# temp_sensors_array_A.net
KiCad netlist of a schematic drawn in EAGLE
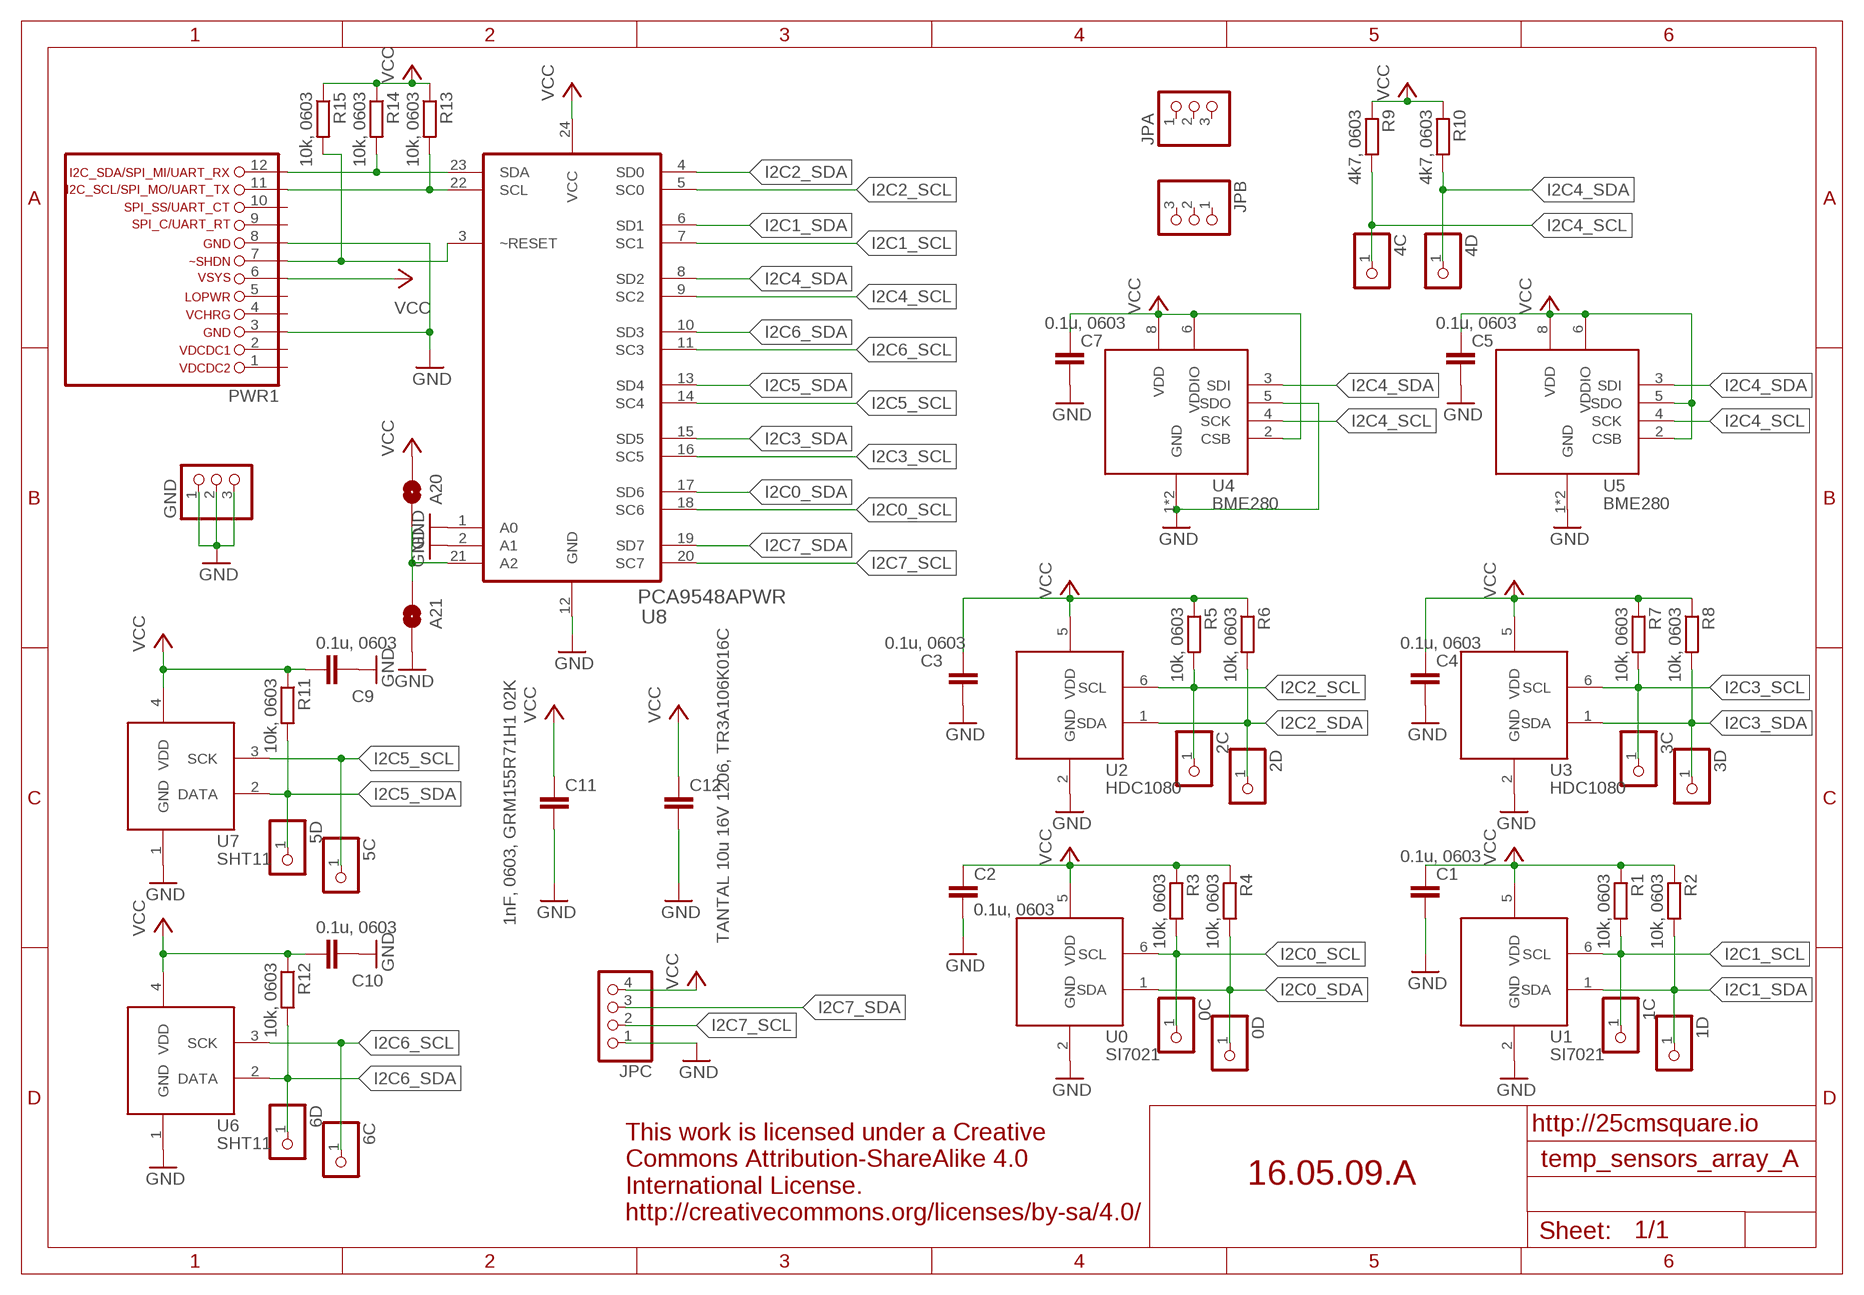
[diagram p0: schematic, sheet 1]

(export (version "E")
  (design (tool "Eeschema 10.0.6"))
  (components
    (comp (ref "0C")
      (value "PINHD-1X1")
      (footprint "eagle-import:1X01")
      (libsource (lib "eagle-import") (part "PINHD-1X1"))
    )
    (comp (ref "0D")
      (value "PINHD-1X1")
      (footprint "eagle-import:1X01")
      (libsource (lib "eagle-import") (part "PINHD-1X1"))
    )
    (comp (ref "1C")
      (value "PINHD-1X1")
      (footprint "eagle-import:1X01")
      (libsource (lib "eagle-import") (part "PINHD-1X1"))
    )
    (comp (ref "1D")
      (value "PINHD-1X1")
      (footprint "eagle-import:1X01")
      (libsource (lib "eagle-import") (part "PINHD-1X1"))
    )
    (comp (ref "2C")
      (value "PINHD-1X1")
      (footprint "eagle-import:1X01")
      (libsource (lib "eagle-import") (part "PINHD-1X1"))
    )
    (comp (ref "2D")
      (value "PINHD-1X1")
      (footprint "eagle-import:1X01")
      (libsource (lib "eagle-import") (part "PINHD-1X1"))
    )
    (comp (ref "3C")
      (value "PINHD-1X1")
      (footprint "eagle-import:1X01")
      (libsource (lib "eagle-import") (part "PINHD-1X1"))
    )
    (comp (ref "3D")
      (value "PINHD-1X1")
      (footprint "eagle-import:1X01")
      (libsource (lib "eagle-import") (part "PINHD-1X1"))
    )
    (comp (ref "4C")
      (value "PINHD-1X1")
      (footprint "eagle-import:1X01")
      (libsource (lib "eagle-import") (part "PINHD-1X1"))
    )
    (comp (ref "4D")
      (value "PINHD-1X1")
      (footprint "eagle-import:1X01")
      (libsource (lib "eagle-import") (part "PINHD-1X1"))
    )
    (comp (ref "5C")
      (value "PINHD-1X1")
      (footprint "eagle-import:1X01")
      (libsource (lib "eagle-import") (part "PINHD-1X1"))
    )
    (comp (ref "5D")
      (value "PINHD-1X1")
      (footprint "eagle-import:1X01")
      (libsource (lib "eagle-import") (part "PINHD-1X1"))
    )
    (comp (ref "6C")
      (value "PINHD-1X1")
      (footprint "eagle-import:1X01")
      (libsource (lib "eagle-import") (part "PINHD-1X1"))
    )
    (comp (ref "6D")
      (value "PINHD-1X1")
      (footprint "eagle-import:1X01")
      (libsource (lib "eagle-import") (part "PINHD-1X1"))
    )
    (comp (ref "A20")
      (value "SOLDERJUMPERNO")
      (footprint "eagle-import:SJ_2S-NO")
      (libsource (lib "eagle-import") (part "SOLDERJUMPERNO"))
    )
    (comp (ref "A21")
      (value "SOLDERJUMPERNO")
      (footprint "eagle-import:SJ_2S-NO")
      (libsource (lib "eagle-import") (part "SOLDERJUMPERNO"))
    )
    (comp (ref "C1")
      (value "0.1u, 0603")
      (footprint "eagle-import:C0603K")
      (libsource (lib "eagle-import") (part "C-EUC0603K"))
    )
    (comp (ref "C2")
      (value "0.1u, 0603")
      (footprint "eagle-import:C0603K")
      (libsource (lib "eagle-import") (part "C-EUC0603K"))
    )
    (comp (ref "C3")
      (value "0.1u, 0603")
      (footprint "eagle-import:C0603K")
      (libsource (lib "eagle-import") (part "C-EUC0603K"))
    )
    (comp (ref "C4")
      (value "0.1u, 0603")
      (footprint "eagle-import:C0603K")
      (libsource (lib "eagle-import") (part "C-EUC0603K"))
    )
    (comp (ref "C5")
      (value "0.1u, 0603")
      (footprint "eagle-import:C0603K")
      (libsource (lib "eagle-import") (part "C-EUC0603K"))
    )
    (comp (ref "C7")
      (value "0.1u, 0603")
      (footprint "eagle-import:C0603K")
      (libsource (lib "eagle-import") (part "C-EUC0603K"))
    )
    (comp (ref "C9")
      (value "0.1u, 0603")
      (footprint "eagle-import:C0603K")
      (libsource (lib "eagle-import") (part "C-EUC0603K"))
    )
    (comp (ref "C10")
      (value "0.1u, 0603")
      (footprint "eagle-import:C0603K")
      (libsource (lib "eagle-import") (part "C-EUC0603K"))
    )
    (comp (ref "C11")
      (value "1nF, 0603, GRM155R71H1 02K")
      (footprint "eagle-import:C0603K")
      (libsource (lib "eagle-import") (part "C-EUC0603K"))
    )
    (comp (ref "C12")
      (value "TANTAL 10u 16V 1206, TR3A106K016C")
      (footprint "eagle-import:C1206K")
      (libsource (lib "eagle-import") (part "resistor_C-EUC1206K"))
    )
    (comp (ref "GND")
      (value "PINHD-1X3")
      (footprint "eagle-import:1X03")
      (libsource (lib "eagle-import") (part "PINHD-1X3"))
    )
    (comp (ref "JPA")
      (value "PINHD-1X3")
      (footprint "eagle-import:1X03")
      (libsource (lib "eagle-import") (part "PINHD-1X3"))
    )
    (comp (ref "JPB")
      (value "PINHD-1X3")
      (footprint "eagle-import:1X03")
      (libsource (lib "eagle-import") (part "PINHD-1X3"))
    )
    (comp (ref "JPC")
      (value "PINHD-1X4")
      (footprint "eagle-import:1X04")
      (libsource (lib "eagle-import") (part "PINHD-1X4"))
    )
    (comp (ref "PWR1")
      (value "LIWE_12_PIN_PWR")
      (footprint "eagle-import:LIWE_12_PIN")
      (libsource (lib "eagle-import") (part "LIWE_12_PIN_PWR"))
    )
    (comp (ref "R1")
      (value "10k, 0603")
      (footprint "eagle-import:R0603")
      (libsource (lib "eagle-import") (part "R-EU_R0603"))
    )
    (comp (ref "R2")
      (value "10k, 0603")
      (footprint "eagle-import:R0603")
      (libsource (lib "eagle-import") (part "R-EU_R0603"))
    )
    (comp (ref "R3")
      (value "10k, 0603")
      (footprint "eagle-import:R0603")
      (libsource (lib "eagle-import") (part "R-EU_R0603"))
    )
    (comp (ref "R4")
      (value "10k, 0603")
      (footprint "eagle-import:R0603")
      (libsource (lib "eagle-import") (part "R-EU_R0603"))
    )
    (comp (ref "R5")
      (value "10k, 0603")
      (footprint "eagle-import:R0603")
      (libsource (lib "eagle-import") (part "R-EU_R0603"))
    )
    (comp (ref "R6")
      (value "10k, 0603")
      (footprint "eagle-import:R0603")
      (libsource (lib "eagle-import") (part "R-EU_R0603"))
    )
    (comp (ref "R7")
      (value "10k, 0603")
      (footprint "eagle-import:R0603")
      (libsource (lib "eagle-import") (part "R-EU_R0603"))
    )
    (comp (ref "R8")
      (value "10k, 0603")
      (footprint "eagle-import:R0603")
      (libsource (lib "eagle-import") (part "R-EU_R0603"))
    )
    (comp (ref "R9")
      (value "4k7, 0603")
      (footprint "eagle-import:R0603")
      (libsource (lib "eagle-import") (part "R-EU_R0603"))
    )
    (comp (ref "R10")
      (value "4k7, 0603")
      (footprint "eagle-import:R0603")
      (libsource (lib "eagle-import") (part "R-EU_R0603"))
    )
    (comp (ref "R11")
      (value "10k, 0603")
      (footprint "eagle-import:R0603")
      (libsource (lib "eagle-import") (part "R-EU_R0603"))
    )
    (comp (ref "R12")
      (value "10k, 0603")
      (footprint "eagle-import:R0603")
      (libsource (lib "eagle-import") (part "R-EU_R0603"))
    )
    (comp (ref "R13")
      (value "10k, 0603")
      (footprint "eagle-import:R0603")
      (libsource (lib "eagle-import") (part "R-EU_R0603"))
    )
    (comp (ref "R14")
      (value "10k, 0603")
      (footprint "eagle-import:R0603")
      (libsource (lib "eagle-import") (part "R-EU_R0603"))
    )
    (comp (ref "R15")
      (value "10k, 0603")
      (footprint "eagle-import:R0603")
      (libsource (lib "eagle-import") (part "R-EU_R0603"))
    )
    (comp (ref "U0")
      (value "SI7021")
      (footprint "eagle-import:SI7021")
      (libsource (lib "eagle-import") (part "SI7021"))
    )
    (comp (ref "U1")
      (value "SI7021")
      (footprint "eagle-import:SI7021")
      (libsource (lib "eagle-import") (part "SI7021"))
    )
    (comp (ref "U2")
      (value "HDC1080")
      (footprint "eagle-import:SI7021")
      (libsource (lib "eagle-import") (part "HDC1080"))
    )
    (comp (ref "U3")
      (value "HDC1080")
      (footprint "eagle-import:SI7021")
      (libsource (lib "eagle-import") (part "HDC1080"))
    )
    (comp (ref "U4")
      (value "BME280")
      (footprint "eagle-import:BME1080")
      (libsource (lib "eagle-import") (part "BME280"))
    )
    (comp (ref "U5")
      (value "BME280")
      (footprint "eagle-import:BME1080")
      (libsource (lib "eagle-import") (part "BME280"))
    )
    (comp (ref "U6")
      (value "SHT11")
      (footprint "eagle-import:SHT1X")
      (libsource (lib "eagle-import") (part "SHT11"))
    )
    (comp (ref "U7")
      (value "SHT11")
      (footprint "eagle-import:SHT1X")
      (libsource (lib "eagle-import") (part "SHT11"))
    )
    (comp (ref "U8")
      (value "PCA9548APWR")
      (footprint "eagle-import:SOP65P640X120-24N")
      (fields (field (name "MPN") "PCA9548APWR    False"))
      (libsource (lib "eagle-import") (part "PCA9548APWR"))
    )
  )
  (nets
    (net (code "1") (name "GND") (class "Default")
      (node (ref "A21") (pin "2") (pinfunction "2_2") (pintype "passive"))
      (node (ref "C1") (pin "2") (pinfunction "2_2") (pintype "passive"))
      (node (ref "C10") (pin "2") (pinfunction "2_2") (pintype "passive"))
      (node (ref "C11") (pin "2") (pinfunction "2_2") (pintype "passive"))
      (node (ref "C12") (pin "2") (pinfunction "2_2") (pintype "passive"))
      (node (ref "C2") (pin "2") (pinfunction "2_2") (pintype "passive"))
      (node (ref "C3") (pin "2") (pinfunction "2_2") (pintype "passive"))
      (node (ref "C4") (pin "2") (pinfunction "2_2") (pintype "passive"))
      (node (ref "C5") (pin "2") (pinfunction "2_2") (pintype "passive"))
      (node (ref "C7") (pin "2") (pinfunction "2_2") (pintype "passive"))
      (node (ref "C9") (pin "2") (pinfunction "2_2") (pintype "passive"))
      (node (ref "GND") (pin "1") (pinfunction "1_1") (pintype "passive"))
      (node (ref "GND") (pin "2") (pinfunction "2_2") (pintype "passive"))
      (node (ref "GND") (pin "3") (pinfunction "3_3") (pintype "passive"))
      (node (ref "JPC") (pin "1") (pinfunction "1_1") (pintype "passive"))
      (node (ref "PWR1") (pin "3") (pinfunction "3_3") (pintype "passive"))
      (node (ref "PWR1") (pin "8") (pinfunction "8_8") (pintype "passive"))
      (node (ref "U0") (pin "2") (pinfunction "GND_2") (pintype "power_in"))
      (node (ref "U1") (pin "2") (pinfunction "GND_2") (pintype "power_in"))
      (node (ref "U2") (pin "2") (pinfunction "GND_2") (pintype "power_in"))
      (node (ref "U3") (pin "2") (pinfunction "GND_2") (pintype "power_in"))
      (node (ref "U4") (pin "1") (pinfunction "GND_1") (pintype "power_in"))
      (node (ref "U4") (pin "5") (pinfunction "SDO_5") (pintype "bidirectional"))
      (node (ref "U4") (pin "7") (pinfunction "GND_7") (pintype "power_in"))
      (node (ref "U5") (pin "1") (pinfunction "GND_1") (pintype "power_in"))
      (node (ref "U5") (pin "7") (pinfunction "GND_7") (pintype "power_in"))
      (node (ref "U6") (pin "1") (pinfunction "GND_1") (pintype "power_in"))
      (node (ref "U7") (pin "1") (pinfunction "GND_1") (pintype "power_in"))
      (node (ref "U8") (pin "1") (pinfunction "A0_1") (pintype "input"))
      (node (ref "U8") (pin "12") (pinfunction "GND_12") (pintype "passive"))
      (node (ref "U8") (pin "2") (pinfunction "A1_2") (pintype "input"))
    )
    (net (code "2") (name "I2C0_SCL") (class "Default")
      (node (ref "0C") (pin "1") (pinfunction "1_1") (pintype "passive"))
      (node (ref "R3") (pin "2") (pinfunction "2_2") (pintype "passive"))
      (node (ref "U0") (pin "6") (pinfunction "SCL_6") (pintype "bidirectional"))
      (node (ref "U8") (pin "18") (pinfunction "SC6_18") (pintype "bidirectional"))
    )
    (net (code "3") (name "I2C0_SDA") (class "Default")
      (node (ref "0D") (pin "1") (pinfunction "1_1") (pintype "passive"))
      (node (ref "R4") (pin "2") (pinfunction "2_2") (pintype "passive"))
      (node (ref "U0") (pin "1") (pinfunction "SDA_1") (pintype "bidirectional"))
      (node (ref "U8") (pin "17") (pinfunction "SD6_17") (pintype "bidirectional"))
    )
    (net (code "4") (name "I2C1_SCL") (class "Default")
      (node (ref "1C") (pin "1") (pinfunction "1_1") (pintype "passive"))
      (node (ref "R1") (pin "2") (pinfunction "2_2") (pintype "passive"))
      (node (ref "U1") (pin "6") (pinfunction "SCL_6") (pintype "bidirectional"))
      (node (ref "U8") (pin "7") (pinfunction "SC1_7") (pintype "bidirectional"))
    )
    (net (code "5") (name "I2C1_SDA") (class "Default")
      (node (ref "1D") (pin "1") (pinfunction "1_1") (pintype "passive"))
      (node (ref "R2") (pin "2") (pinfunction "2_2") (pintype "passive"))
      (node (ref "U1") (pin "1") (pinfunction "SDA_1") (pintype "bidirectional"))
      (node (ref "U8") (pin "6") (pinfunction "SD1_6") (pintype "bidirectional"))
    )
    (net (code "6") (name "I2C2_SCL") (class "Default")
      (node (ref "2C") (pin "1") (pinfunction "1_1") (pintype "passive"))
      (node (ref "R5") (pin "2") (pinfunction "2_2") (pintype "passive"))
      (node (ref "U2") (pin "6") (pinfunction "SCL_6") (pintype "bidirectional"))
      (node (ref "U8") (pin "5") (pinfunction "SC0_5") (pintype "bidirectional"))
    )
    (net (code "7") (name "I2C2_SDA") (class "Default")
      (node (ref "2D") (pin "1") (pinfunction "1_1") (pintype "passive"))
      (node (ref "R6") (pin "2") (pinfunction "2_2") (pintype "passive"))
      (node (ref "U2") (pin "1") (pinfunction "SDA_1") (pintype "bidirectional"))
      (node (ref "U8") (pin "4") (pinfunction "SD0_4") (pintype "bidirectional"))
    )
    (net (code "8") (name "I2C3_SCL") (class "Default")
      (node (ref "3C") (pin "1") (pinfunction "1_1") (pintype "passive"))
      (node (ref "R7") (pin "2") (pinfunction "2_2") (pintype "passive"))
      (node (ref "U3") (pin "6") (pinfunction "SCL_6") (pintype "bidirectional"))
      (node (ref "U8") (pin "16") (pinfunction "SC5_16") (pintype "bidirectional"))
    )
    (net (code "9") (name "I2C3_SDA") (class "Default")
      (node (ref "3D") (pin "1") (pinfunction "1_1") (pintype "passive"))
      (node (ref "R8") (pin "2") (pinfunction "2_2") (pintype "passive"))
      (node (ref "U3") (pin "1") (pinfunction "SDA_1") (pintype "bidirectional"))
      (node (ref "U8") (pin "15") (pinfunction "SD5_15") (pintype "bidirectional"))
    )
    (net (code "10") (name "I2C4_SCL") (class "Default")
      (node (ref "4C") (pin "1") (pinfunction "1_1") (pintype "passive"))
      (node (ref "R9") (pin "2") (pinfunction "2_2") (pintype "passive"))
      (node (ref "U4") (pin "4") (pinfunction "SCK_4") (pintype "bidirectional"))
      (node (ref "U5") (pin "4") (pinfunction "SCK_4") (pintype "bidirectional"))
      (node (ref "U8") (pin "9") (pinfunction "SC2_9") (pintype "bidirectional"))
    )
    (net (code "11") (name "I2C4_SDA") (class "Default")
      (node (ref "4D") (pin "1") (pinfunction "1_1") (pintype "passive"))
      (node (ref "R10") (pin "2") (pinfunction "2_2") (pintype "passive"))
      (node (ref "U4") (pin "3") (pinfunction "SDI_3") (pintype "bidirectional"))
      (node (ref "U5") (pin "3") (pinfunction "SDI_3") (pintype "bidirectional"))
      (node (ref "U8") (pin "8") (pinfunction "SD2_8") (pintype "bidirectional"))
    )
    (net (code "12") (name "I2C5_SCL") (class "Default")
      (node (ref "5C") (pin "1") (pinfunction "1_1") (pintype "passive"))
      (node (ref "U7") (pin "3") (pinfunction "SCK_3") (pintype "bidirectional"))
      (node (ref "U8") (pin "14") (pinfunction "SC4_14") (pintype "bidirectional"))
    )
    (net (code "13") (name "I2C5_SDA") (class "Default")
      (node (ref "5D") (pin "1") (pinfunction "1_1") (pintype "passive"))
      (node (ref "R11") (pin "2") (pinfunction "2_2") (pintype "passive"))
      (node (ref "U7") (pin "2") (pinfunction "DATA_2") (pintype "bidirectional"))
      (node (ref "U8") (pin "13") (pinfunction "SD4_13") (pintype "bidirectional"))
    )
    (net (code "14") (name "I2C6_SCL") (class "Default")
      (node (ref "6C") (pin "1") (pinfunction "1_1") (pintype "passive"))
      (node (ref "U6") (pin "3") (pinfunction "SCK_3") (pintype "bidirectional"))
      (node (ref "U8") (pin "11") (pinfunction "SC3_11") (pintype "bidirectional"))
    )
    (net (code "15") (name "I2C6_SDA") (class "Default")
      (node (ref "6D") (pin "1") (pinfunction "1_1") (pintype "passive"))
      (node (ref "R12") (pin "2") (pinfunction "2_2") (pintype "passive"))
      (node (ref "U6") (pin "2") (pinfunction "DATA_2") (pintype "bidirectional"))
      (node (ref "U8") (pin "10") (pinfunction "SD3_10") (pintype "bidirectional"))
    )
    (net (code "16") (name "I2C7_SCL") (class "Default")
      (node (ref "JPC") (pin "2") (pinfunction "2_2") (pintype "passive"))
      (node (ref "U8") (pin "20") (pinfunction "SC7_20") (pintype "bidirectional"))
    )
    (net (code "17") (name "I2C7_SDA") (class "Default")
      (node (ref "JPC") (pin "3") (pinfunction "3_3") (pintype "passive"))
      (node (ref "U8") (pin "19") (pinfunction "SD7_19") (pintype "bidirectional"))
    )
    (net (code "18") (name "Net-(U8-A2)") (class "Default")
      (node (ref "A20") (pin "2") (pinfunction "2_2") (pintype "passive"))
      (node (ref "A21") (pin "1") (pinfunction "1_1") (pintype "passive"))
      (node (ref "U8") (pin "21") (pinfunction "A2_21") (pintype "input"))
    )
    (net (code "19") (name "Net-(U8-SCL)") (class "Default")
      (node (ref "PWR1") (pin "11") (pinfunction "11_11") (pintype "passive"))
      (node (ref "R13") (pin "2") (pinfunction "2_2") (pintype "passive"))
      (node (ref "U8") (pin "22") (pinfunction "SCL_22") (pintype "input"))
    )
    (net (code "20") (name "Net-(U8-SDA)") (class "Default")
      (node (ref "PWR1") (pin "12") (pinfunction "12_12") (pintype "passive"))
      (node (ref "R14") (pin "2") (pinfunction "2_2") (pintype "passive"))
      (node (ref "U8") (pin "23") (pinfunction "SDA_23") (pintype "bidirectional"))
    )
    (net (code "21") (name "Net-(U8-~{RESET})") (class "Default")
      (node (ref "PWR1") (pin "7") (pinfunction "7_7") (pintype "passive"))
      (node (ref "R15") (pin "2") (pinfunction "2_2") (pintype "passive"))
      (node (ref "U8") (pin "3") (pinfunction "~{RESET}_3") (pintype "input"))
    )
    (net (code "22") (name "VCC") (class "Default")
      (node (ref "A20") (pin "1") (pinfunction "1_1") (pintype "passive"))
      (node (ref "C1") (pin "1") (pinfunction "1_1") (pintype "passive"))
      (node (ref "C10") (pin "1") (pinfunction "1_1") (pintype "passive"))
      (node (ref "C11") (pin "1") (pinfunction "1_1") (pintype "passive"))
      (node (ref "C12") (pin "1") (pinfunction "1_1") (pintype "passive"))
      (node (ref "C2") (pin "1") (pinfunction "1_1") (pintype "passive"))
      (node (ref "C3") (pin "1") (pinfunction "1_1") (pintype "passive"))
      (node (ref "C4") (pin "1") (pinfunction "1_1") (pintype "passive"))
      (node (ref "C5") (pin "1") (pinfunction "1_1") (pintype "passive"))
      (node (ref "C7") (pin "1") (pinfunction "1_1") (pintype "passive"))
      (node (ref "C9") (pin "1") (pinfunction "1_1") (pintype "passive"))
      (node (ref "JPC") (pin "4") (pinfunction "4_4") (pintype "passive"))
      (node (ref "PWR1") (pin "6") (pinfunction "6_6") (pintype "passive"))
      (node (ref "R1") (pin "1") (pinfunction "1_1") (pintype "passive"))
      (node (ref "R10") (pin "1") (pinfunction "1_1") (pintype "passive"))
      (node (ref "R11") (pin "1") (pinfunction "1_1") (pintype "passive"))
      (node (ref "R12") (pin "1") (pinfunction "1_1") (pintype "passive"))
      (node (ref "R13") (pin "1") (pinfunction "1_1") (pintype "passive"))
      (node (ref "R14") (pin "1") (pinfunction "1_1") (pintype "passive"))
      (node (ref "R15") (pin "1") (pinfunction "1_1") (pintype "passive"))
      (node (ref "R2") (pin "1") (pinfunction "1_1") (pintype "passive"))
      (node (ref "R3") (pin "1") (pinfunction "1_1") (pintype "passive"))
      (node (ref "R4") (pin "1") (pinfunction "1_1") (pintype "passive"))
      (node (ref "R5") (pin "1") (pinfunction "1_1") (pintype "passive"))
      (node (ref "R6") (pin "1") (pinfunction "1_1") (pintype "passive"))
      (node (ref "R7") (pin "1") (pinfunction "1_1") (pintype "passive"))
      (node (ref "R8") (pin "1") (pinfunction "1_1") (pintype "passive"))
      (node (ref "R9") (pin "1") (pinfunction "1_1") (pintype "passive"))
      (node (ref "U0") (pin "5") (pinfunction "VDD_5") (pintype "power_in"))
      (node (ref "U1") (pin "5") (pinfunction "VDD_5") (pintype "power_in"))
      (node (ref "U2") (pin "5") (pinfunction "VDD_5") (pintype "power_in"))
      (node (ref "U3") (pin "5") (pinfunction "VDD_5") (pintype "power_in"))
      (node (ref "U4") (pin "2") (pinfunction "CSB_2") (pintype "bidirectional"))
      (node (ref "U4") (pin "6") (pinfunction "VDDIO_6") (pintype "power_in"))
      (node (ref "U4") (pin "8") (pinfunction "VDD_8") (pintype "power_in"))
      (node (ref "U5") (pin "2") (pinfunction "CSB_2") (pintype "bidirectional"))
      (node (ref "U5") (pin "5") (pinfunction "SDO_5") (pintype "bidirectional"))
      (node (ref "U5") (pin "6") (pinfunction "VDDIO_6") (pintype "power_in"))
      (node (ref "U5") (pin "8") (pinfunction "VDD_8") (pintype "power_in"))
      (node (ref "U6") (pin "4") (pinfunction "VDD_4") (pintype "power_in"))
      (node (ref "U7") (pin "4") (pinfunction "VDD_4") (pintype "power_in"))
      (node (ref "U8") (pin "24") (pinfunction "VCC_24") (pintype "power_in"))
    )
    (net (code "23") (name "unconnected-(JPA-Pad1)") (class "Default")
      (node (ref "JPA") (pin "1") (pinfunction "1_1") (pintype "passive"))
    )
    (net (code "24") (name "unconnected-(JPA-Pad2)") (class "Default")
      (node (ref "JPA") (pin "2") (pinfunction "2_2") (pintype "passive"))
    )
    (net (code "25") (name "unconnected-(JPA-Pad3)") (class "Default")
      (node (ref "JPA") (pin "3") (pinfunction "3_3") (pintype "passive"))
    )
    (net (code "26") (name "unconnected-(JPB-Pad1)") (class "Default")
      (node (ref "JPB") (pin "1") (pinfunction "1_1") (pintype "passive"))
    )
    (net (code "27") (name "unconnected-(JPB-Pad2)") (class "Default")
      (node (ref "JPB") (pin "2") (pinfunction "2_2") (pintype "passive"))
    )
    (net (code "28") (name "unconnected-(JPB-Pad3)") (class "Default")
      (node (ref "JPB") (pin "3") (pinfunction "3_3") (pintype "passive"))
    )
    (net (code "29") (name "unconnected-(PWR1-Pad1)") (class "Default")
      (node (ref "PWR1") (pin "1") (pinfunction "1_1") (pintype "passive"))
    )
    (net (code "30") (name "unconnected-(PWR1-Pad2)") (class "Default")
      (node (ref "PWR1") (pin "2") (pinfunction "2_2") (pintype "passive"))
    )
    (net (code "31") (name "unconnected-(PWR1-Pad4)") (class "Default")
      (node (ref "PWR1") (pin "4") (pinfunction "4_4") (pintype "passive"))
    )
    (net (code "32") (name "unconnected-(PWR1-Pad5)") (class "Default")
      (node (ref "PWR1") (pin "5") (pinfunction "5_5") (pintype "passive"))
    )
    (net (code "33") (name "unconnected-(PWR1-Pad9)") (class "Default")
      (node (ref "PWR1") (pin "9") (pinfunction "9_9") (pintype "passive"))
    )
    (net (code "34") (name "unconnected-(PWR1-Pad10)") (class "Default")
      (node (ref "PWR1") (pin "10") (pinfunction "10_10") (pintype "passive"))
    )
  )
)
